# LED_Driver.net
KiCad netlist of a schematic drawn in Altium Designer
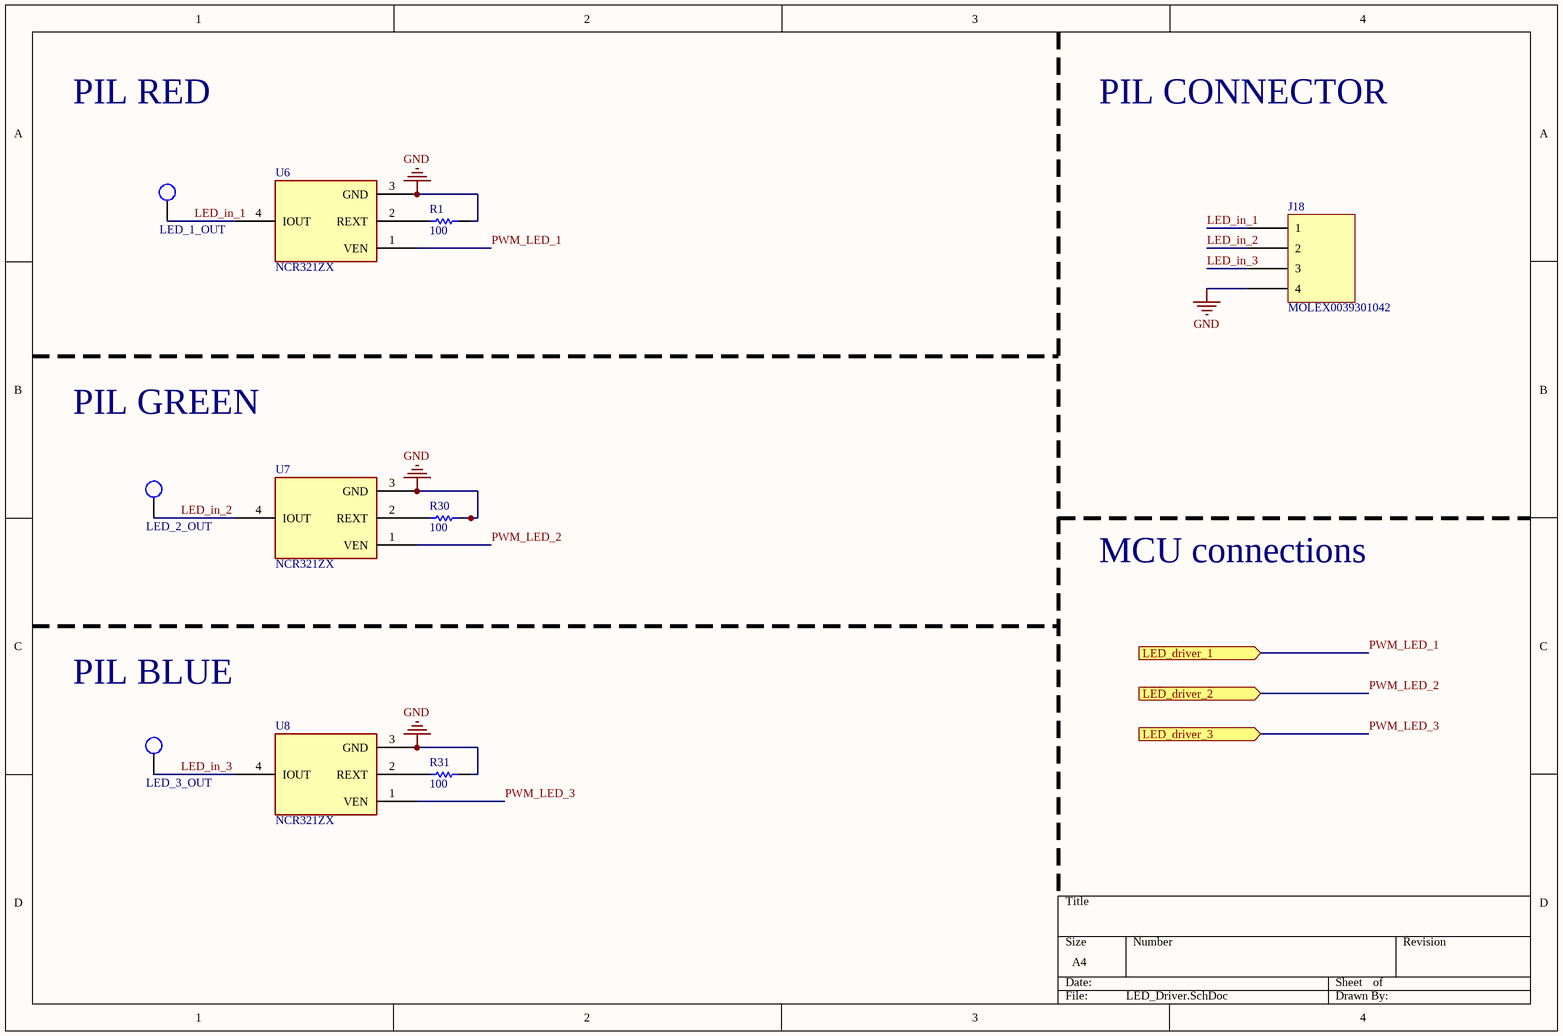
[diagram p0: LED_Driver.SchDoc]

(export (version "E")
  (design (tool "Eeschema 10.0.6"))
  (components
    (comp (ref "J18")
      (value "MOLEX0039301042")
      (footprint "MOLEX0039301042")
      (description "Connector Header Through Hole, Right Angle 4 position 0.165\" (4.20mm)")
      (fields (field (name "MANUFACTURER") "Molex") (field (name "MANUFACTURER PART NUMBER") "0039301042"))
      (libsource (lib "GeneralConnectors") (part "MOLEX0039301042"))
    )
    (comp (ref "LED_1_OUT")
      (value "Test Point")
      (footprint "Test Point - 5002")
      (libsource (lib "General") (part "Test Point"))
    )
    (comp (ref "LED_2_OUT")
      (value "Test Point")
      (footprint "Test Point - 5002")
      (libsource (lib "General") (part "Test Point"))
    )
    (comp (ref "LED_3_OUT")
      (value "Test Point")
      (footprint "Test Point - 5002")
      (libsource (lib "General") (part "Test Point"))
    )
    (comp (ref "R1")
      (value "100")
      (footprint "0805 - Resistor")
      (description "Resistor")
      (libsource (lib "General") (part "Resistor"))
    )
    (comp (ref "R30")
      (value "100")
      (footprint "0805 - Resistor")
      (description "Resistor")
      (libsource (lib "General") (part "Resistor"))
    )
    (comp (ref "R31")
      (value "100")
      (footprint "0805 - Resistor")
      (description "Resistor")
      (libsource (lib "General") (part "Resistor"))
    )
    (comp (ref "U6")
      (value "NCR321ZX")
      (footprint "NCR321ZX LED driver")
      (description "IC LED DRVR LIN PWM 250MA SOT223")
      (libsource (lib "Embedded") (part "NCR321ZX"))
    )
    (comp (ref "U7")
      (value "NCR321ZX")
      (footprint "NCR321ZX LED driver")
      (description "IC LED DRVR LIN PWM 250MA SOT223")
      (libsource (lib "Embedded") (part "NCR321ZX"))
    )
    (comp (ref "U8")
      (value "NCR321ZX")
      (footprint "NCR321ZX LED driver")
      (description "IC LED DRVR LIN PWM 250MA SOT223")
      (libsource (lib "Embedded") (part "NCR321ZX"))
    )
  )
  (nets
    (net (code "1") (name "/LED_in_1") (class "Default")
      (node (ref "J18") (pin "1") (pinfunction "1_1") (pintype "passive"))
      (node (ref "LED_1_OUT") (pin "1") (pinfunction "0_1") (pintype "passive"))
      (node (ref "U6") (pin "4") (pinfunction "IOUT_4") (pintype "passive"))
    )
    (net (code "2") (name "/LED_in_2") (class "Default")
      (node (ref "J18") (pin "2") (pinfunction "2_2") (pintype "passive"))
      (node (ref "LED_2_OUT") (pin "1") (pinfunction "0_1") (pintype "passive"))
      (node (ref "U7") (pin "4") (pinfunction "IOUT_4") (pintype "passive"))
    )
    (net (code "3") (name "/LED_in_3") (class "Default")
      (node (ref "J18") (pin "3") (pinfunction "3_3") (pintype "passive"))
      (node (ref "LED_3_OUT") (pin "1") (pinfunction "0_1") (pintype "passive"))
      (node (ref "U8") (pin "4") (pinfunction "IOUT_4") (pintype "passive"))
    )
    (net (code "4") (name "/PWM_LED_1") (class "Default")
      (node (ref "U6") (pin "1") (pinfunction "VEN_1") (pintype "passive"))
    )
    (net (code "5") (name "/PWM_LED_2") (class "Default")
      (node (ref "U7") (pin "1") (pinfunction "VEN_1") (pintype "passive"))
    )
    (net (code "6") (name "/PWM_LED_3") (class "Default")
      (node (ref "U8") (pin "1") (pinfunction "VEN_1") (pintype "passive"))
    )
    (net (code "7") (name "GND") (class "Default")
      (node (ref "J18") (pin "4") (pinfunction "4_4") (pintype "passive"))
      (node (ref "R1") (pin "2") (pinfunction "2_2") (pintype "passive"))
      (node (ref "R30") (pin "2") (pinfunction "2_2") (pintype "passive"))
      (node (ref "R31") (pin "2") (pinfunction "2_2") (pintype "passive"))
      (node (ref "U6") (pin "3") (pinfunction "GND_3") (pintype "power_in"))
      (node (ref "U7") (pin "3") (pinfunction "GND_3") (pintype "power_in"))
      (node (ref "U8") (pin "3") (pinfunction "GND_3") (pintype "power_in"))
    )
    (net (code "8") (name "Net-(U6-REXT)") (class "Default")
      (node (ref "R1") (pin "1") (pinfunction "1_1") (pintype "passive"))
      (node (ref "U6") (pin "2") (pinfunction "REXT_2") (pintype "passive"))
    )
    (net (code "9") (name "Net-(U7-REXT)") (class "Default")
      (node (ref "R30") (pin "1") (pinfunction "1_1") (pintype "passive"))
      (node (ref "U7") (pin "2") (pinfunction "REXT_2") (pintype "passive"))
    )
    (net (code "10") (name "Net-(U8-REXT)") (class "Default")
      (node (ref "R31") (pin "1") (pinfunction "1_1") (pintype "passive"))
      (node (ref "U8") (pin "2") (pinfunction "REXT_2") (pintype "passive"))
    )
  )
)
